# avr.net
KiCad netlist of a schematic drawn in EAGLE
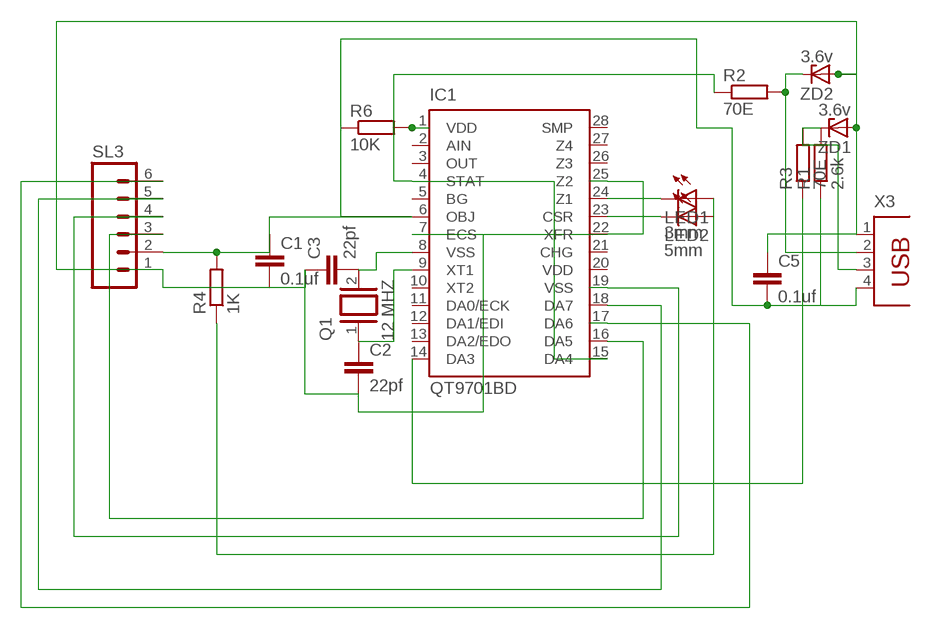
[diagram p0: schematic, sheet 1]

(export (version "E")
  (design (tool "Eeschema 10.0.6"))
  (components
    (comp (ref "C1")
      (value "0.1uf")
      (footprint "eagle-import:C2.5-3")
      (libsource (lib "eagle-import") (part "C2,5-3"))
    )
    (comp (ref "C2")
      (value "22pf")
      (footprint "eagle-import:C2.5-3")
      (libsource (lib "eagle-import") (part "C2,5-3"))
    )
    (comp (ref "C3")
      (value "22pf")
      (footprint "eagle-import:C2.5-3")
      (libsource (lib "eagle-import") (part "C2,5-3"))
    )
    (comp (ref "C5")
      (value "0.1uf")
      (footprint "eagle-import:C2.5-3")
      (libsource (lib "eagle-import") (part "C2,5-3"))
    )
    (comp (ref "IC1")
      (value "QT9701BD")
      (footprint "eagle-import:DIL28-3")
      (libsource (lib "eagle-import") (part "QT9701BD"))
    )
    (comp (ref "LED1")
      (value "3mm")
      (footprint "eagle-import:LED3MM")
      (libsource (lib "eagle-import") (part "LED3MM"))
    )
    (comp (ref "LED2")
      (value "5mm")
      (footprint "eagle-import:LED3MM")
      (libsource (lib "eagle-import") (part "LED3MM"))
    )
    (comp (ref "Q1")
      (value "12 MHZ")
      (footprint "eagle-import:QS")
      (libsource (lib "eagle-import") (part "XTAL/S"))
    )
    (comp (ref "R1")
      (value "2.6k")
      (footprint "eagle-import:0204_7")
      (libsource (lib "eagle-import") (part "R-EU_0204/7"))
    )
    (comp (ref "R2")
      (value "70E")
      (footprint "eagle-import:0204_7")
      (libsource (lib "eagle-import") (part "R-EU_0204/7"))
    )
    (comp (ref "R3")
      (value "70E")
      (footprint "eagle-import:0204_7")
      (libsource (lib "eagle-import") (part "R-EU_0204/7"))
    )
    (comp (ref "R4")
      (value "1K")
      (footprint "eagle-import:0204_7")
      (libsource (lib "eagle-import") (part "R-EU_0204/7"))
    )
    (comp (ref "R6")
      (value "10K")
      (footprint "eagle-import:0204_7")
      (libsource (lib "eagle-import") (part "R-EU_0204/7"))
    )
    (comp (ref "SL3")
      (value "M06")
      (footprint "eagle-import:06P")
      (libsource (lib "eagle-import") (part "M06"))
    )
    (comp (ref "X3")
      (value "PN87520")
      (footprint "eagle-import:PN87520")
      (libsource (lib "eagle-import") (part "PN87520"))
    )
    (comp (ref "ZD1")
      (value "3.6v")
      (footprint "eagle-import:SOD81")
      (libsource (lib "eagle-import") (part "BZD23"))
    )
    (comp (ref "ZD2")
      (value "3.6v")
      (footprint "eagle-import:SOD81")
      (libsource (lib "eagle-import") (part "BZD23"))
    )
  )
  (nets
    (net (code "1") (name "Net-(C3-Pad2)") (class "Default")
      (node (ref "C3") (pin "2") (pinfunction "2_2") (pintype "passive"))
      (node (ref "IC1") (pin "8") (pinfunction "VSS_8") (pintype "input"))
      (node (ref "Q1") (pin "2") (pinfunction "2_2") (pintype "passive"))
    )
    (net (code "2") (name "Net-(IC1-CSR)") (class "Default")
      (node (ref "IC1") (pin "23") (pinfunction "CSR_23") (pintype "output"))
      (node (ref "LED2") (pin "K") (pinfunction "C_K") (pintype "passive"))
    )
    (net (code "3") (name "Net-(IC1-DA3)") (class "Default")
      (node (ref "IC1") (pin "14") (pinfunction "DA3_14") (pintype "output"))
      (node (ref "R3") (pin "1") (pinfunction "1_1") (pintype "passive"))
    )
    (net (code "4") (name "Net-(IC1-DA4)") (class "Default")
      (node (ref "IC1") (pin "15") (pinfunction "DA4_15") (pintype "output"))
      (node (ref "IC1") (pin "4") (pinfunction "STAT_4") (pintype "output"))
      (node (ref "R2") (pin "1") (pinfunction "1_1") (pintype "passive"))
    )
    (net (code "5") (name "Net-(IC1-DA5)") (class "Default")
      (node (ref "IC1") (pin "16") (pinfunction "DA5_16") (pintype "output"))
      (node (ref "SL3") (pin "3") (pinfunction "3_3") (pintype "passive"))
    )
    (net (code "6") (name "Net-(IC1-DA6)") (class "Default")
      (node (ref "IC1") (pin "17") (pinfunction "DA6_17") (pintype "output"))
      (node (ref "SL3") (pin "6") (pinfunction "6_6") (pintype "passive"))
    )
    (net (code "7") (name "Net-(IC1-DA7)") (class "Default")
      (node (ref "IC1") (pin "18") (pinfunction "DA7_18") (pintype "output"))
      (node (ref "SL3") (pin "5") (pinfunction "5_5") (pintype "passive"))
    )
    (net (code "8") (name "Net-(IC1-ECS)") (class "Default")
      (node (ref "C1") (pin "2") (pinfunction "2_2") (pintype "passive"))
      (node (ref "C2") (pin "2") (pinfunction "2_2") (pintype "passive"))
      (node (ref "C3") (pin "1") (pinfunction "1_1") (pintype "passive"))
      (node (ref "C5") (pin "1") (pinfunction "1_1") (pintype "passive"))
      (node (ref "IC1") (pin "22") (pinfunction "XFR_22") (pintype "output"))
      (node (ref "IC1") (pin "25") (pinfunction "Z2_25") (pintype "output"))
      (node (ref "IC1") (pin "7") (pinfunction "ECS_7") (pintype "output"))
      (node (ref "SL3") (pin "1") (pinfunction "1_1") (pintype "passive"))
      (node (ref "X3") (pin "1") (pinfunction "1_1") (pintype "passive"))
      (node (ref "ZD1") (pin "A") (pinfunction "A_A") (pintype "passive"))
      (node (ref "ZD2") (pin "A") (pinfunction "A_A") (pintype "passive"))
    )
    (net (code "9") (name "Net-(IC1-OBJ)") (class "Default")
      (node (ref "C1") (pin "1") (pinfunction "1_1") (pintype "passive"))
      (node (ref "C5") (pin "2") (pinfunction "2_2") (pintype "passive"))
      (node (ref "IC1") (pin "6") (pinfunction "OBJ_6") (pintype "input"))
      (node (ref "R1") (pin "1") (pinfunction "1_1") (pintype "passive"))
      (node (ref "R4") (pin "2") (pinfunction "2_2") (pintype "passive"))
      (node (ref "R6") (pin "1") (pinfunction "1_1") (pintype "passive"))
      (node (ref "SL3") (pin "2") (pinfunction "2_2") (pintype "passive"))
      (node (ref "X3") (pin "4") (pinfunction "4_4") (pintype "passive"))
    )
    (net (code "10") (name "Net-(IC1-VDD-Pad1)") (class "Default")
      (node (ref "IC1") (pin "1") (pinfunction "VDD_1") (pintype "input"))
      (node (ref "R6") (pin "2") (pinfunction "2_2") (pintype "passive"))
    )
    (net (code "11") (name "Net-(IC1-VSS-Pad19)") (class "Default")
      (node (ref "IC1") (pin "19") (pinfunction "VSS_19") (pintype "input"))
      (node (ref "SL3") (pin "4") (pinfunction "4_4") (pintype "passive"))
    )
    (net (code "12") (name "Net-(IC1-XT1)") (class "Default")
      (node (ref "C2") (pin "1") (pinfunction "1_1") (pintype "passive"))
      (node (ref "IC1") (pin "9") (pinfunction "XT1_9") (pintype "input"))
      (node (ref "Q1") (pin "1") (pinfunction "1_1") (pintype "passive"))
    )
    (net (code "13") (name "Net-(IC1-Z1)") (class "Default")
      (node (ref "IC1") (pin "24") (pinfunction "Z1_24") (pintype "output"))
      (node (ref "LED1") (pin "K") (pinfunction "C_K") (pintype "passive"))
    )
    (net (code "14") (name "Net-(LED1-PadA)") (class "Default")
      (node (ref "LED1") (pin "A") (pinfunction "A_A") (pintype "passive"))
      (node (ref "LED2") (pin "A") (pinfunction "A_A") (pintype "passive"))
      (node (ref "R4") (pin "1") (pinfunction "1_1") (pintype "passive"))
    )
    (net (code "15") (name "Net-(R1-Pad2)") (class "Default")
      (node (ref "R1") (pin "2") (pinfunction "2_2") (pintype "passive"))
      (node (ref "R3") (pin "2") (pinfunction "2_2") (pintype "passive"))
      (node (ref "X3") (pin "3") (pinfunction "3_3") (pintype "passive"))
      (node (ref "ZD1") (pin "C") (pinfunction "C_C") (pintype "passive"))
    )
    (net (code "16") (name "Net-(R2-Pad2)") (class "Default")
      (node (ref "R2") (pin "2") (pinfunction "2_2") (pintype "passive"))
      (node (ref "X3") (pin "2") (pinfunction "2_2") (pintype "passive"))
      (node (ref "ZD2") (pin "C") (pinfunction "C_C") (pintype "passive"))
    )
    (net (code "17") (name "unconnected-(IC1-AIN-Pad2)") (class "Default")
      (node (ref "IC1") (pin "2") (pinfunction "AIN_2") (pintype "input"))
    )
    (net (code "18") (name "unconnected-(IC1-BG-Pad5)") (class "Default")
      (node (ref "IC1") (pin "5") (pinfunction "BG_5") (pintype "input"))
    )
    (net (code "19") (name "unconnected-(IC1-CHG-Pad21)") (class "Default")
      (node (ref "IC1") (pin "21") (pinfunction "CHG_21") (pintype "output"))
    )
    (net (code "20") (name "unconnected-(IC1-DA0{slash}ECK-Pad11)") (class "Default")
      (node (ref "IC1") (pin "11") (pinfunction "DA0/ECK_11") (pintype "output"))
    )
    (net (code "21") (name "unconnected-(IC1-DA1{slash}EDI-Pad12)") (class "Default")
      (node (ref "IC1") (pin "12") (pinfunction "DA1/EDI_12") (pintype "output"))
    )
    (net (code "22") (name "unconnected-(IC1-DA2{slash}EDO-Pad13)") (class "Default")
      (node (ref "IC1") (pin "13") (pinfunction "DA2/EDO_13") (pintype "output"))
    )
    (net (code "23") (name "unconnected-(IC1-OUT-Pad3)") (class "Default")
      (node (ref "IC1") (pin "3") (pinfunction "OUT_3") (pintype "output"))
    )
    (net (code "24") (name "unconnected-(IC1-SMP-Pad28)") (class "Default")
      (node (ref "IC1") (pin "28") (pinfunction "SMP_28") (pintype "output"))
    )
    (net (code "25") (name "unconnected-(IC1-VDD-Pad20)") (class "Default")
      (node (ref "IC1") (pin "20") (pinfunction "VDD_20") (pintype "input"))
    )
    (net (code "26") (name "unconnected-(IC1-XT2-Pad10)") (class "Default")
      (node (ref "IC1") (pin "10") (pinfunction "XT2_10") (pintype "output"))
    )
    (net (code "27") (name "unconnected-(IC1-Z3-Pad26)") (class "Default")
      (node (ref "IC1") (pin "26") (pinfunction "Z3_26") (pintype "output"))
    )
    (net (code "28") (name "unconnected-(IC1-Z4-Pad27)") (class "Default")
      (node (ref "IC1") (pin "27") (pinfunction "Z4_27") (pintype "output"))
    )
  )
)
